# RaspberryPi_Connections.net
KiCad netlist of a schematic drawn in EAGLE
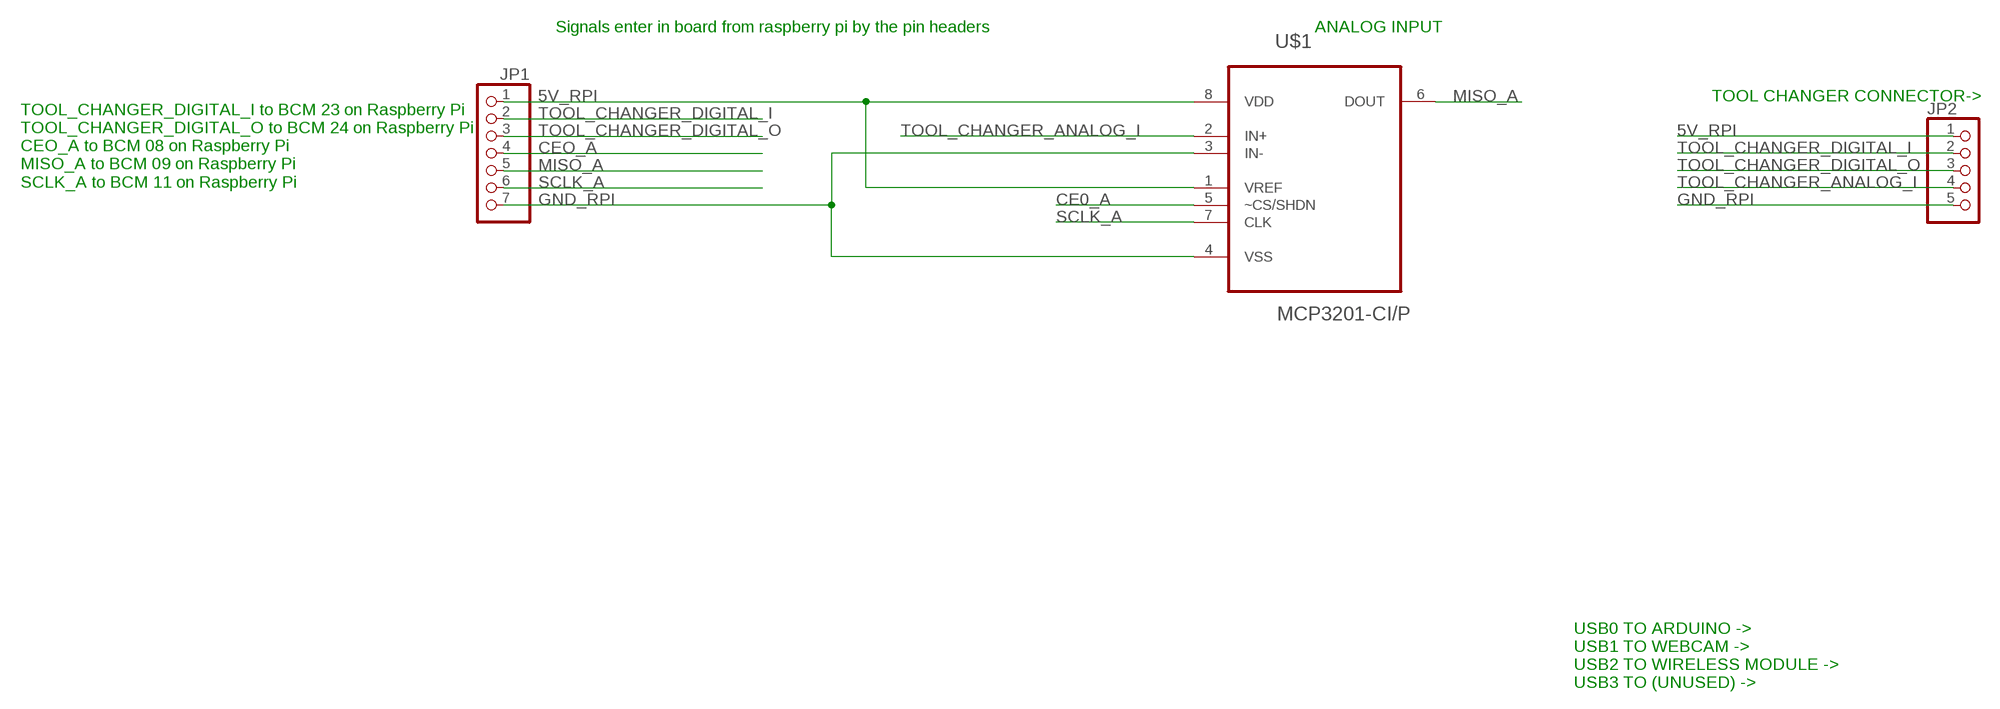
[diagram p0: schematic, sheet 1]

(export (version "E")
  (design (tool "Eeschema 10.0.6"))
  (components
    (comp (ref "JP1")
      (value "PINHD-1X7")
      (footprint "eagle-import:1X07")
      (libsource (lib "eagle-import") (part "PINHD-1X7"))
    )
    (comp (ref "JP2")
      (value "PINHD-1X5")
      (footprint "eagle-import:1X05")
      (libsource (lib "eagle-import") (part "PINHD-1X5"))
    )
    (comp (ref "U$1")
      (value "MCP3201-CI/P")
      (footprint "eagle-import:DIP254P762X533-8")
      (fields (field (name "MF") "Microchip"))
      (libsource (lib "eagle-import") (part "MCP3201-CI/P"))
    )
  )
  (nets
    (net (code "1") (name "/5V_RPI") (class "Default")
      (node (ref "JP1") (pin "1") (pinfunction "1_1") (pintype "passive"))
      (node (ref "JP2") (pin "1") (pinfunction "1_1") (pintype "passive"))
      (node (ref "U$1") (pin "1") (pinfunction "VREF_1") (pintype "input"))
      (node (ref "U$1") (pin "8") (pinfunction "VDD_8") (pintype "power_in"))
    )
    (net (code "2") (name "/CE0_A") (class "Default")
      (node (ref "U$1") (pin "5") (pinfunction "~{CS/SHDN}_5") (pintype "input"))
    )
    (net (code "3") (name "/CEO_A") (class "Default")
      (node (ref "JP1") (pin "4") (pinfunction "4_4") (pintype "passive"))
    )
    (net (code "4") (name "/GND_RPI") (class "Default")
      (node (ref "JP1") (pin "7") (pinfunction "7_7") (pintype "passive"))
      (node (ref "JP2") (pin "5") (pinfunction "5_5") (pintype "passive"))
      (node (ref "U$1") (pin "3") (pinfunction "IN-_3") (pintype "input"))
      (node (ref "U$1") (pin "4") (pinfunction "VSS_4") (pintype "passive"))
    )
    (net (code "5") (name "/MISO_A") (class "Default")
      (node (ref "JP1") (pin "5") (pinfunction "5_5") (pintype "passive"))
      (node (ref "U$1") (pin "6") (pinfunction "DOUT_6") (pintype "output"))
    )
    (net (code "6") (name "/SCLK_A") (class "Default")
      (node (ref "JP1") (pin "6") (pinfunction "6_6") (pintype "passive"))
      (node (ref "U$1") (pin "7") (pinfunction "CLK_7") (pintype "input"))
    )
    (net (code "7") (name "/TOOL_CHANGER_ANALOG_I") (class "Default")
      (node (ref "JP2") (pin "4") (pinfunction "4_4") (pintype "passive"))
      (node (ref "U$1") (pin "2") (pinfunction "IN+_2") (pintype "input"))
    )
    (net (code "8") (name "/TOOL_CHANGER_DIGITAL_I") (class "Default")
      (node (ref "JP1") (pin "2") (pinfunction "2_2") (pintype "passive"))
      (node (ref "JP2") (pin "2") (pinfunction "2_2") (pintype "passive"))
    )
    (net (code "9") (name "/TOOL_CHANGER_DIGITAL_O") (class "Default")
      (node (ref "JP1") (pin "3") (pinfunction "3_3") (pintype "passive"))
      (node (ref "JP2") (pin "3") (pinfunction "3_3") (pintype "passive"))
    )
  )
)
